# PowerboardV2.net
KiCad netlist of a schematic drawn in Altium Designer
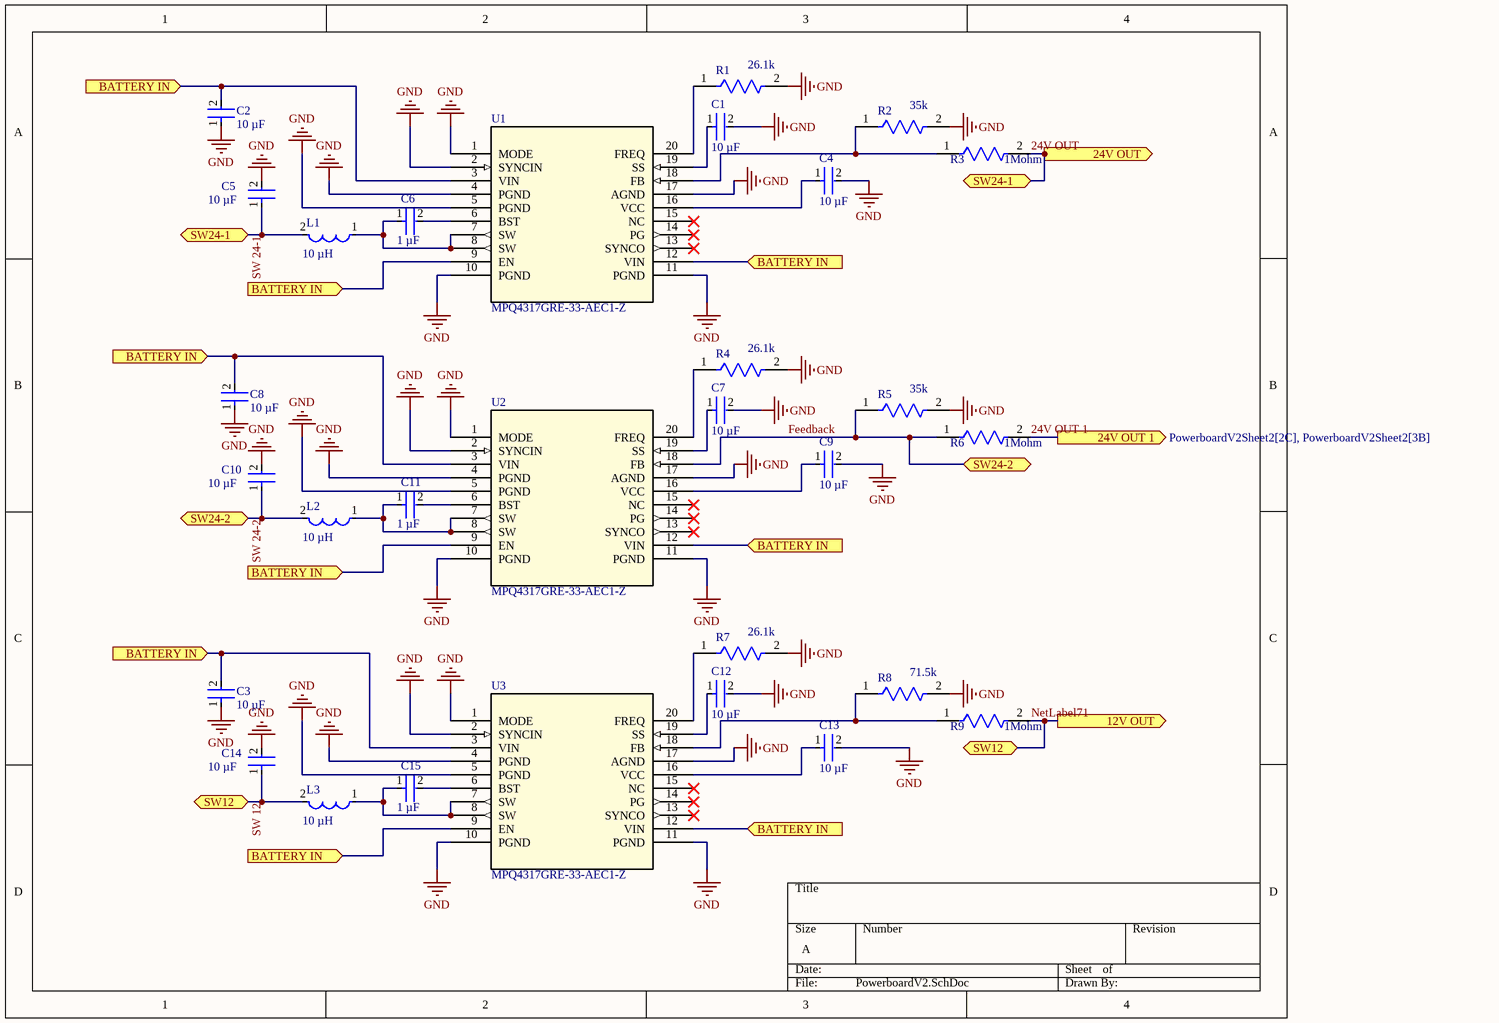
[diagram p0: PowerboardV2.SchDoc]

(export (version "E")
  (design (tool "Eeschema 10.0.6"))
  (components
    (comp (ref "C1")
      (value "10 µF")
      (footprint "FP-C0805C-DG-MFG")
      (description "CAP CER 10UF 10V X5R 0805")
      (fields (field (name "TOLERANCE") "10%") (field (name "MANUFACTURER PART NUMBER") "C0805C106K8PACTU"))
      (libsource (lib "Altium Content Vault") (part "11868f565c42a9108669ba33697ecf6"))
    )
    (comp (ref "C2")
      (value "10 µF")
      (footprint "FP-C0805C-DG-MFG")
      (description "CAP CER 10UF 10V X5R 0805")
      (fields (field (name "TOLERANCE") "10%") (field (name "MANUFACTURER PART NUMBER") "C0805C106K8PACTU"))
      (libsource (lib "Altium Content Vault") (part "11868f565c42a9108669ba33697ecf6"))
    )
    (comp (ref "C3")
      (value "10 µF")
      (footprint "FP-C0805C-DG-MFG")
      (description "CAP CER 10UF 10V X5R 0805")
      (fields (field (name "TOLERANCE") "10%") (field (name "MANUFACTURER PART NUMBER") "C0805C106K8PACTU"))
      (libsource (lib "Altium Content Vault") (part "11868f565c42a9108669ba33697ecf6"))
    )
    (comp (ref "C4")
      (value "10 µF")
      (footprint "FP-C0805C-DG-MFG")
      (description "CAP CER 10UF 10V X5R 0805")
      (fields (field (name "TOLERANCE") "10%") (field (name "MANUFACTURER PART NUMBER") "C0805C106K8PACTU"))
      (libsource (lib "Altium Content Vault") (part "11868f565c42a9108669ba33697ecf6"))
    )
    (comp (ref "C5")
      (value "10 µF")
      (footprint "FP-C0805C-DG-MFG")
      (description "CAP CER 10UF 10V X5R 0805")
      (fields (field (name "TOLERANCE") "10%") (field (name "MANUFACTURER PART NUMBER") "C0805C106K8PACTU"))
      (libsource (lib "Altium Content Vault") (part "11868f565c42a9108669ba33697ecf6"))
    )
    (comp (ref "C6")
      (value "1 µF")
      (footprint "FP-C0805C-DG-MFG")
      (description "CAP CER 10UF 10V X5R 0805")
      (fields (field (name "TOLERANCE") "10%") (field (name "MANUFACTURER PART NUMBER") "C0805C106K8PACTU"))
      (libsource (lib "Altium Content Vault") (part "11868f565c42a9108669ba33697ecf6"))
    )
    (comp (ref "C7")
      (value "10 µF")
      (footprint "FP-C0805C-DG-MFG")
      (description "CAP CER 10UF 10V X5R 0805")
      (fields (field (name "TOLERANCE") "10%") (field (name "MANUFACTURER PART NUMBER") "C0805C106K8PACTU"))
      (libsource (lib "Altium Content Vault") (part "11868f565c42a9108669ba33697ecf6"))
    )
    (comp (ref "C8")
      (value "10 µF")
      (footprint "FP-C0805C-DG-MFG")
      (description "CAP CER 10UF 10V X5R 0805")
      (fields (field (name "TOLERANCE") "10%") (field (name "MANUFACTURER PART NUMBER") "C0805C106K8PACTU"))
      (libsource (lib "Altium Content Vault") (part "11868f565c42a9108669ba33697ecf6"))
    )
    (comp (ref "C9")
      (value "10 µF")
      (footprint "FP-C0805C-DG-MFG")
      (description "CAP CER 10UF 10V X5R 0805")
      (fields (field (name "TOLERANCE") "10%") (field (name "MANUFACTURER PART NUMBER") "C0805C106K8PACTU"))
      (libsource (lib "Altium Content Vault") (part "11868f565c42a9108669ba33697ecf6"))
    )
    (comp (ref "C10")
      (value "10 µF")
      (footprint "FP-C0805C-DG-MFG")
      (description "CAP CER 10UF 10V X5R 0805")
      (fields (field (name "TOLERANCE") "10%") (field (name "MANUFACTURER PART NUMBER") "C0805C106K8PACTU"))
      (libsource (lib "Altium Content Vault") (part "11868f565c42a9108669ba33697ecf6"))
    )
    (comp (ref "C11")
      (value "1 µF")
      (footprint "FP-C0805C-DG-MFG")
      (description "CAP CER 10UF 10V X5R 0805")
      (fields (field (name "TOLERANCE") "10%") (field (name "MANUFACTURER PART NUMBER") "C0805C106K8PACTU"))
      (libsource (lib "Altium Content Vault") (part "11868f565c42a9108669ba33697ecf6"))
    )
    (comp (ref "C12")
      (value "10 µF")
      (footprint "FP-C0805C-DG-MFG")
      (description "CAP CER 10UF 10V X5R 0805")
      (fields (field (name "TOLERANCE") "10%") (field (name "MANUFACTURER PART NUMBER") "C0805C106K8PACTU"))
      (libsource (lib "Altium Content Vault") (part "11868f565c42a9108669ba33697ecf6"))
    )
    (comp (ref "C13")
      (value "10 µF")
      (footprint "FP-C0805C-DG-MFG")
      (description "CAP CER 10UF 10V X5R 0805")
      (fields (field (name "TOLERANCE") "10%") (field (name "MANUFACTURER PART NUMBER") "C0805C106K8PACTU"))
      (libsource (lib "Altium Content Vault") (part "11868f565c42a9108669ba33697ecf6"))
    )
    (comp (ref "C14")
      (value "10 µF")
      (footprint "FP-C0805C-DG-MFG")
      (description "CAP CER 10UF 10V X5R 0805")
      (fields (field (name "TOLERANCE") "10%") (field (name "MANUFACTURER PART NUMBER") "C0805C106K8PACTU"))
      (libsource (lib "Altium Content Vault") (part "11868f565c42a9108669ba33697ecf6"))
    )
    (comp (ref "C15")
      (value "1 µF")
      (footprint "FP-C0805C-DG-MFG")
      (description "CAP CER 10UF 10V X5R 0805")
      (fields (field (name "TOLERANCE") "10%") (field (name "MANUFACTURER PART NUMBER") "C0805C106K8PACTU"))
      (libsource (lib "Altium Content Vault") (part "11868f565c42a9108669ba33697ecf6"))
    )
    (comp (ref "L1")
      (value "10 µH")
      (footprint "FP-IHLP-5050FD-FP_2_945x4-MFG")
      (description "FIXED IND 10UH 10A 17.2 MOHM SMD")
      (fields (field (name "TOLERANCE") "20%"))
      (libsource (lib "Altium Content Vault") (part "725321dda6339637d4d059423bc1c3c"))
    )
    (comp (ref "L2")
      (value "10 µH")
      (footprint "FP-IHLP-5050FD-FP_2_945x4-MFG")
      (description "FIXED IND 10UH 10A 17.2 MOHM SMD")
      (fields (field (name "TOLERANCE") "20%"))
      (libsource (lib "Altium Content Vault") (part "725321dda6339637d4d059423bc1c3c"))
    )
    (comp (ref "L3")
      (value "10 µH")
      (footprint "FP-IHLP-5050FD-FP_2_945x4-MFG")
      (description "FIXED IND 10UH 10A 17.2 MOHM SMD")
      (fields (field (name "TOLERANCE") "20%"))
      (libsource (lib "Altium Content Vault") (part "725321dda6339637d4d059423bc1c3c"))
    )
    (comp (ref "R1")
      (value "26.1k")
      (footprint "FP-CRCW0805-e3-IPC_B")
      (description "RES Thick Film, 1MΩ, 1%, 0.125W, 100ppm/°C, 0805")
      (fields (field (name "TOLERANCE") "1%"))
      (libsource (lib "Altium Content Vault") (part "1029c3af85768c4190bb7ad29bc67b5"))
    )
    (comp (ref "R2")
      (value "35k")
      (footprint "FP-CRCW0805-e3-IPC_B")
      (description "RES Thick Film, 1MΩ, 1%, 0.125W, 100ppm/°C, 0805")
      (fields (field (name "TOLERANCE") "1%"))
      (libsource (lib "Altium Content Vault") (part "1029c3af85768c4190bb7ad29bc67b5"))
    )
    (comp (ref "R3")
      (value "1Mohm")
      (footprint "FP-CRCW0805-e3-IPC_B")
      (description "RES Thick Film, 1MΩ, 1%, 0.125W, 100ppm/°C, 0805")
      (fields (field (name "TOLERANCE") "1%"))
      (libsource (lib "Altium Content Vault") (part "1029c3af85768c4190bb7ad29bc67b5"))
    )
    (comp (ref "R4")
      (value "26.1k")
      (footprint "FP-CRCW0805-e3-IPC_B")
      (description "RES Thick Film, 1MΩ, 1%, 0.125W, 100ppm/°C, 0805")
      (fields (field (name "TOLERANCE") "1%"))
      (libsource (lib "Altium Content Vault") (part "1029c3af85768c4190bb7ad29bc67b5"))
    )
    (comp (ref "R5")
      (value "35k")
      (footprint "FP-CRCW0805-e3-IPC_B")
      (description "RES Thick Film, 1MΩ, 1%, 0.125W, 100ppm/°C, 0805")
      (fields (field (name "TOLERANCE") "1%"))
      (libsource (lib "Altium Content Vault") (part "1029c3af85768c4190bb7ad29bc67b5"))
    )
    (comp (ref "R6")
      (value "1Mohm")
      (footprint "FP-CRCW0805-e3-IPC_B")
      (description "RES Thick Film, 1MΩ, 1%, 0.125W, 100ppm/°C, 0805")
      (fields (field (name "TOLERANCE") "1%"))
      (libsource (lib "Altium Content Vault") (part "1029c3af85768c4190bb7ad29bc67b5"))
    )
    (comp (ref "R7")
      (value "26.1k")
      (footprint "FP-CRCW0805-e3-IPC_B")
      (description "RES Thick Film, 1MΩ, 1%, 0.125W, 100ppm/°C, 0805")
      (fields (field (name "TOLERANCE") "1%"))
      (libsource (lib "Altium Content Vault") (part "1029c3af85768c4190bb7ad29bc67b5"))
    )
    (comp (ref "R8")
      (value "71.5k")
      (footprint "FP-CRCW0805-e3-IPC_B")
      (description "RES Thick Film, 1MΩ, 1%, 0.125W, 100ppm/°C, 0805")
      (fields (field (name "TOLERANCE") "1%"))
      (libsource (lib "Altium Content Vault") (part "1029c3af85768c4190bb7ad29bc67b5"))
    )
    (comp (ref "R9")
      (value "1Mohm")
      (footprint "FP-CRCW0805-e3-IPC_B")
      (description "RES Thick Film, 1MΩ, 1%, 0.125W, 100ppm/°C, 0805")
      (fields (field (name "TOLERANCE") "1%"))
      (libsource (lib "Altium Content Vault") (part "1029c3af85768c4190bb7ad29bc67b5"))
    )
    (comp (ref "U1")
      (value "MPQ4317GRE-33-AEC1-Z")
      (footprint "QFN-20_MPQ4317_MNP")
      (description "No Description Available")
      (fields (field (name "COPYRIGHT") "Copyright (C) 2023 Ultra Librarian. All rights reserved."))
      (libsource (lib "MPQ4317GRE-33-AEC1-Z") (part "MPQ4317GRE-33-AEC1-Z"))
    )
    (comp (ref "U2")
      (value "MPQ4317GRE-33-AEC1-Z")
      (footprint "QFN-20_MPQ4317_MNP")
      (description "No Description Available")
      (fields (field (name "COPYRIGHT") "Copyright (C) 2023 Ultra Librarian. All rights reserved."))
      (libsource (lib "MPQ4317GRE-33-AEC1-Z") (part "MPQ4317GRE-33-AEC1-Z"))
    )
    (comp (ref "U3")
      (value "MPQ4317GRE-33-AEC1-Z")
      (footprint "QFN-20_MPQ4317_MNP")
      (description "No Description Available")
      (fields (field (name "COPYRIGHT") "Copyright (C) 2023 Ultra Librarian. All rights reserved."))
      (libsource (lib "MPQ4317GRE-33-AEC1-Z") (part "MPQ4317GRE-33-AEC1-Z"))
    )
  )
  (nets
    (net (code "1") (name "/24V OUT") (class "Default")
      (node (ref "C5") (pin "1") (pinfunction "1_1") (pintype "passive"))
      (node (ref "L1") (pin "2") (pinfunction "2_2") (pintype "passive"))
      (node (ref "R3") (pin "2") (pinfunction "2_2") (pintype "passive"))
    )
    (net (code "2") (name "/24V OUT 1") (class "Default")
      (node (ref "R6") (pin "2") (pinfunction "2_2") (pintype "passive"))
    )
    (net (code "3") (name "/BATTERY IN") (class "Default")
      (node (ref "C2") (pin "2") (pinfunction "2_2") (pintype "passive"))
      (node (ref "C3") (pin "2") (pinfunction "2_2") (pintype "passive"))
      (node (ref "C8") (pin "2") (pinfunction "2_2") (pintype "passive"))
      (node (ref "U1") (pin "12") (pinfunction "VIN_12") (pintype "power_in"))
      (node (ref "U1") (pin "3") (pinfunction "VIN_3") (pintype "power_in"))
      (node (ref "U1") (pin "9") (pinfunction "EN_9") (pintype "passive"))
      (node (ref "U2") (pin "12") (pinfunction "VIN_12") (pintype "power_in"))
      (node (ref "U2") (pin "3") (pinfunction "VIN_3") (pintype "power_in"))
      (node (ref "U2") (pin "9") (pinfunction "EN_9") (pintype "passive"))
      (node (ref "U3") (pin "12") (pinfunction "VIN_12") (pintype "power_in"))
      (node (ref "U3") (pin "3") (pinfunction "VIN_3") (pintype "power_in"))
      (node (ref "U3") (pin "9") (pinfunction "EN_9") (pintype "passive"))
    )
    (net (code "4") (name "/Feedback") (class "Default")
      (node (ref "C10") (pin "1") (pinfunction "1_1") (pintype "passive"))
      (node (ref "L2") (pin "2") (pinfunction "2_2") (pintype "passive"))
      (node (ref "R5") (pin "1") (pinfunction "1_1") (pintype "passive"))
      (node (ref "R6") (pin "1") (pinfunction "1_1") (pintype "passive"))
      (node (ref "U2") (pin "18") (pinfunction "FB_18") (pintype "input"))
    )
    (net (code "5") (name "/NetLabel71") (class "Default")
      (node (ref "C14") (pin "1") (pinfunction "1_1") (pintype "passive"))
      (node (ref "L3") (pin "2") (pinfunction "2_2") (pintype "passive"))
      (node (ref "R9") (pin "2") (pinfunction "2_2") (pintype "passive"))
    )
    (net (code "6") (name "GND") (class "Default")
      (node (ref "C1") (pin "2") (pinfunction "2_2") (pintype "passive"))
      (node (ref "C10") (pin "2") (pinfunction "2_2") (pintype "passive"))
      (node (ref "C12") (pin "2") (pinfunction "2_2") (pintype "passive"))
      (node (ref "C13") (pin "2") (pinfunction "2_2") (pintype "passive"))
      (node (ref "C14") (pin "2") (pinfunction "2_2") (pintype "passive"))
      (node (ref "C2") (pin "1") (pinfunction "1_1") (pintype "passive"))
      (node (ref "C3") (pin "1") (pinfunction "1_1") (pintype "passive"))
      (node (ref "C4") (pin "2") (pinfunction "2_2") (pintype "passive"))
      (node (ref "C5") (pin "2") (pinfunction "2_2") (pintype "passive"))
      (node (ref "C7") (pin "2") (pinfunction "2_2") (pintype "passive"))
      (node (ref "C8") (pin "1") (pinfunction "1_1") (pintype "passive"))
      (node (ref "C9") (pin "2") (pinfunction "2_2") (pintype "passive"))
      (node (ref "R1") (pin "2") (pinfunction "2_2") (pintype "passive"))
      (node (ref "R2") (pin "2") (pinfunction "2_2") (pintype "passive"))
      (node (ref "R4") (pin "2") (pinfunction "2_2") (pintype "passive"))
      (node (ref "R5") (pin "2") (pinfunction "2_2") (pintype "passive"))
      (node (ref "R7") (pin "2") (pinfunction "2_2") (pintype "passive"))
      (node (ref "R8") (pin "2") (pinfunction "2_2") (pintype "passive"))
      (node (ref "U1") (pin "1") (pinfunction "MODE_1") (pintype "passive"))
      (node (ref "U1") (pin "10") (pinfunction "PGND_10") (pintype "power_in"))
      (node (ref "U1") (pin "11") (pinfunction "PGND_11") (pintype "power_in"))
      (node (ref "U1") (pin "17") (pinfunction "AGND_17") (pintype "power_in"))
      (node (ref "U1") (pin "2") (pinfunction "SYNCIN_2") (pintype "input"))
      (node (ref "U1") (pin "4") (pinfunction "PGND_4") (pintype "power_in"))
      (node (ref "U1") (pin "5") (pinfunction "PGND_5") (pintype "power_in"))
      (node (ref "U2") (pin "1") (pinfunction "MODE_1") (pintype "passive"))
      (node (ref "U2") (pin "10") (pinfunction "PGND_10") (pintype "power_in"))
      (node (ref "U2") (pin "11") (pinfunction "PGND_11") (pintype "power_in"))
      (node (ref "U2") (pin "17") (pinfunction "AGND_17") (pintype "power_in"))
      (node (ref "U2") (pin "2") (pinfunction "SYNCIN_2") (pintype "input"))
      (node (ref "U2") (pin "4") (pinfunction "PGND_4") (pintype "power_in"))
      (node (ref "U2") (pin "5") (pinfunction "PGND_5") (pintype "power_in"))
      (node (ref "U3") (pin "1") (pinfunction "MODE_1") (pintype "passive"))
      (node (ref "U3") (pin "10") (pinfunction "PGND_10") (pintype "power_in"))
      (node (ref "U3") (pin "11") (pinfunction "PGND_11") (pintype "power_in"))
      (node (ref "U3") (pin "17") (pinfunction "AGND_17") (pintype "power_in"))
      (node (ref "U3") (pin "2") (pinfunction "SYNCIN_2") (pintype "input"))
      (node (ref "U3") (pin "4") (pinfunction "PGND_4") (pintype "power_in"))
      (node (ref "U3") (pin "5") (pinfunction "PGND_5") (pintype "power_in"))
    )
    (net (code "7") (name "Net-(C6-Pad1)") (class "Default")
      (node (ref "C6") (pin "1") (pinfunction "1_1") (pintype "passive"))
      (node (ref "L1") (pin "1") (pinfunction "1_1") (pintype "passive"))
      (node (ref "U1") (pin "7") (pinfunction "SW_7") (pintype "output"))
      (node (ref "U1") (pin "8") (pinfunction "SW_8") (pintype "output"))
    )
    (net (code "8") (name "Net-(C11-Pad1)") (class "Default")
      (node (ref "C11") (pin "1") (pinfunction "1_1") (pintype "passive"))
      (node (ref "L2") (pin "1") (pinfunction "1_1") (pintype "passive"))
      (node (ref "U2") (pin "7") (pinfunction "SW_7") (pintype "output"))
      (node (ref "U2") (pin "8") (pinfunction "SW_8") (pintype "output"))
    )
    (net (code "9") (name "Net-(C15-Pad1)") (class "Default")
      (node (ref "C15") (pin "1") (pinfunction "1_1") (pintype "passive"))
      (node (ref "L3") (pin "1") (pinfunction "1_1") (pintype "passive"))
      (node (ref "U3") (pin "7") (pinfunction "SW_7") (pintype "output"))
      (node (ref "U3") (pin "8") (pinfunction "SW_8") (pintype "output"))
    )
    (net (code "10") (name "Net-(U1-BST)") (class "Default")
      (node (ref "C6") (pin "2") (pinfunction "2_2") (pintype "passive"))
      (node (ref "U1") (pin "6") (pinfunction "BST_6") (pintype "power_in"))
    )
    (net (code "11") (name "Net-(U1-FB)") (class "Default")
      (node (ref "R2") (pin "1") (pinfunction "1_1") (pintype "passive"))
      (node (ref "R3") (pin "1") (pinfunction "1_1") (pintype "passive"))
      (node (ref "U1") (pin "18") (pinfunction "FB_18") (pintype "input"))
    )
    (net (code "12") (name "Net-(U1-FREQ)") (class "Default")
      (node (ref "R1") (pin "1") (pinfunction "1_1") (pintype "passive"))
      (node (ref "U1") (pin "20") (pinfunction "FREQ_20") (pintype "passive"))
    )
    (net (code "13") (name "Net-(U1-SS)") (class "Default")
      (node (ref "C1") (pin "1") (pinfunction "1_1") (pintype "passive"))
      (node (ref "U1") (pin "19") (pinfunction "SS_19") (pintype "input"))
    )
    (net (code "14") (name "Net-(U1-VCC)") (class "Default")
      (node (ref "C4") (pin "1") (pinfunction "1_1") (pintype "passive"))
      (node (ref "U1") (pin "16") (pinfunction "VCC_16") (pintype "power_in"))
    )
    (net (code "15") (name "Net-(U2-BST)") (class "Default")
      (node (ref "C11") (pin "2") (pinfunction "2_2") (pintype "passive"))
      (node (ref "U2") (pin "6") (pinfunction "BST_6") (pintype "power_in"))
    )
    (net (code "16") (name "Net-(U2-FREQ)") (class "Default")
      (node (ref "R4") (pin "1") (pinfunction "1_1") (pintype "passive"))
      (node (ref "U2") (pin "20") (pinfunction "FREQ_20") (pintype "passive"))
    )
    (net (code "17") (name "Net-(U2-SS)") (class "Default")
      (node (ref "C7") (pin "1") (pinfunction "1_1") (pintype "passive"))
      (node (ref "U2") (pin "19") (pinfunction "SS_19") (pintype "input"))
    )
    (net (code "18") (name "Net-(U2-VCC)") (class "Default")
      (node (ref "C9") (pin "1") (pinfunction "1_1") (pintype "passive"))
      (node (ref "U2") (pin "16") (pinfunction "VCC_16") (pintype "power_in"))
    )
    (net (code "19") (name "Net-(U3-BST)") (class "Default")
      (node (ref "C15") (pin "2") (pinfunction "2_2") (pintype "passive"))
      (node (ref "U3") (pin "6") (pinfunction "BST_6") (pintype "power_in"))
    )
    (net (code "20") (name "Net-(U3-FB)") (class "Default")
      (node (ref "R8") (pin "1") (pinfunction "1_1") (pintype "passive"))
      (node (ref "R9") (pin "1") (pinfunction "1_1") (pintype "passive"))
      (node (ref "U3") (pin "18") (pinfunction "FB_18") (pintype "input"))
    )
    (net (code "21") (name "Net-(U3-FREQ)") (class "Default")
      (node (ref "R7") (pin "1") (pinfunction "1_1") (pintype "passive"))
      (node (ref "U3") (pin "20") (pinfunction "FREQ_20") (pintype "passive"))
    )
    (net (code "22") (name "Net-(U3-SS)") (class "Default")
      (node (ref "C12") (pin "1") (pinfunction "1_1") (pintype "passive"))
      (node (ref "U3") (pin "19") (pinfunction "SS_19") (pintype "input"))
    )
    (net (code "23") (name "Net-(U3-VCC)") (class "Default")
      (node (ref "C13") (pin "1") (pinfunction "1_1") (pintype "passive"))
      (node (ref "U3") (pin "16") (pinfunction "VCC_16") (pintype "power_in"))
    )
    (net (code "24") (name "unconnected-(U1-NC-Pad15)") (class "Default")
      (node (ref "U1") (pin "15") (pinfunction "NC_15") (pintype "passive+no_connect"))
    )
    (net (code "25") (name "unconnected-(U1-PG-Pad14)") (class "Default")
      (node (ref "U1") (pin "14") (pinfunction "PG_14") (pintype "output+no_connect"))
    )
    (net (code "26") (name "unconnected-(U1-SYNCO-Pad13)") (class "Default")
      (node (ref "U1") (pin "13") (pinfunction "SYNCO_13") (pintype "output+no_connect"))
    )
    (net (code "27") (name "unconnected-(U2-NC-Pad15)") (class "Default")
      (node (ref "U2") (pin "15") (pinfunction "NC_15") (pintype "passive+no_connect"))
    )
    (net (code "28") (name "unconnected-(U2-PG-Pad14)") (class "Default")
      (node (ref "U2") (pin "14") (pinfunction "PG_14") (pintype "output+no_connect"))
    )
    (net (code "29") (name "unconnected-(U2-SYNCO-Pad13)") (class "Default")
      (node (ref "U2") (pin "13") (pinfunction "SYNCO_13") (pintype "output+no_connect"))
    )
    (net (code "30") (name "unconnected-(U3-NC-Pad15)") (class "Default")
      (node (ref "U3") (pin "15") (pinfunction "NC_15") (pintype "passive+no_connect"))
    )
    (net (code "31") (name "unconnected-(U3-PG-Pad14)") (class "Default")
      (node (ref "U3") (pin "14") (pinfunction "PG_14") (pintype "output+no_connect"))
    )
    (net (code "32") (name "unconnected-(U3-SYNCO-Pad13)") (class "Default")
      (node (ref "U3") (pin "13") (pinfunction "SYNCO_13") (pintype "output+no_connect"))
    )
  )
)
